# STM32_MCU.net
KiCad netlist of a schematic drawn in Altium Designer
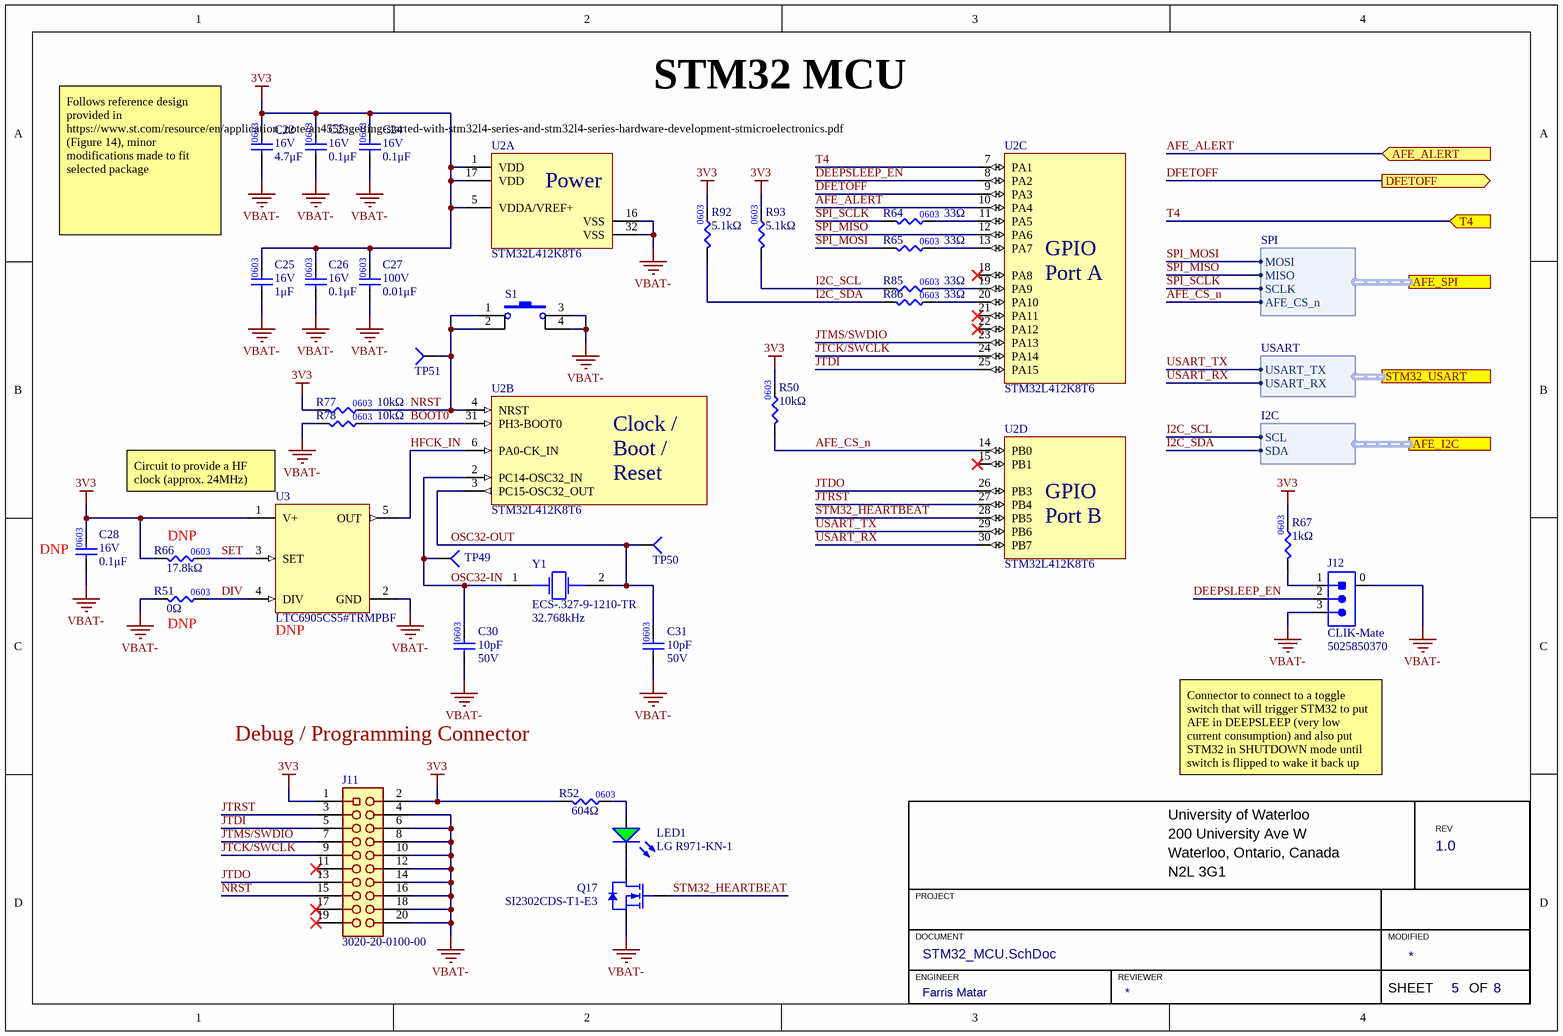
[diagram p0: STM32_MCU.SchDoc]

(export (version "E")
  (design (tool "Eeschema 10.0.6"))
  (components
    (comp (ref "C22")
      (value "4.7μF")
      (footprint "CAP0603")
      (description "CAP CER 4.7UF 16V X6S 0603")
      (fields (field (name "VOLTAGE RATING") "16V") (field (name "Comment") "CAP_4.7uF_16V_0603"))
      (libsource (lib "Personal_Schematic_Library_2022") (part "CAP_4.7uF_16V_0603"))
    )
    (comp (ref "C23")
      (value "0.1μF")
      (footprint "CAP0603")
      (description "CAP CER 0.1UF 16V X7R 0603")
      (fields (field (name "VOLTAGE RATING") "16V") (field (name "Comment") "CAP_0.1uF_16V_0603"))
      (libsource (lib "Personal_Schematic_Library_2022") (part "CAP_0.1uF_16V_0603"))
    )
    (comp (ref "C24")
      (value "0.1μF")
      (footprint "CAP0603")
      (description "CAP CER 0.1UF 16V X7R 0603")
      (fields (field (name "VOLTAGE RATING") "16V") (field (name "Comment") "CAP_0.1uF_16V_0603"))
      (libsource (lib "Personal_Schematic_Library_2022") (part "CAP_0.1uF_16V_0603"))
    )
    (comp (ref "C25")
      (value "1μF")
      (footprint "CAP0603")
      (description "CAP CER 1UF 16V X7R 0603")
      (fields (field (name "VOLTAGE RATING") "16V") (field (name "Comment") "CAP_1uF_16V_0603"))
      (libsource (lib "Personal_Schematic_Library_2022") (part "CAP_1uF_16V_0603"))
    )
    (comp (ref "C26")
      (value "0.1μF")
      (footprint "CAP0603")
      (description "CAP CER 0.1UF 16V X7R 0603")
      (fields (field (name "VOLTAGE RATING") "16V") (field (name "Comment") "CAP_0.1uF_16V_0603"))
      (libsource (lib "Personal_Schematic_Library_2022") (part "CAP_0.1uF_16V_0603"))
    )
    (comp (ref "C27")
      (value "0.01μF")
      (footprint "CAP0603")
      (description "CAP CER 0.01uF 100V X7R 0603")
      (fields (field (name "VOLTAGE RATING") "100V") (field (name "Comment") "CAP_0.01uF_100V_0603"))
      (libsource (lib "Personal_Schematic_Library_2022") (part "CAP_0.01uF_100V_0603"))
    )
    (comp (ref "C28")
      (value "0.1μF")
      (footprint "CAP0603")
      (description "CAP CER 0.1UF 16V X7R 0603")
      (fields (field (name "VOLTAGE RATING") "16V") (field (name "Comment") "CAP_0.1uF_16V_0603"))
      (libsource (lib "Personal_Schematic_Library_2022") (part "CAP_0.1uF_16V_0603"))
    )
    (comp (ref "C30")
      (value "10pF")
      (footprint "CAP0603")
      (description "CAP CER 10PF 50V X7R 0603")
      (fields (field (name "VOLTAGE RATING") "50V") (field (name "Comment") "CAP_10pF_50V_0603"))
      (libsource (lib "Personal_Schematic_Library_2022") (part "CAP_10pF_50V_0603"))
    )
    (comp (ref "C31")
      (value "10pF")
      (footprint "CAP0603")
      (description "CAP CER 10PF 50V X7R 0603")
      (fields (field (name "VOLTAGE RATING") "50V") (field (name "Comment") "CAP_10pF_50V_0603"))
      (libsource (lib "Personal_Schematic_Library_2022") (part "CAP_10pF_50V_0603"))
    )
    (comp (ref "J11")
      (value "3020-20-0100-00")
      (footprint "CNC_3020-20-0100-00")
      (description "CONN HEADER VERT 20POS 2.54MM")
      (libsource (lib "Personal_Schematic_Library_2022") (part "CON_10x2_HEADER"))
    )
    (comp (ref "J12")
      (value "CON_3M_SM_RA")
      (footprint "MOLEX-5025850370")
      (description "CONN RCPT 3POS 0.059 TIN SMD R/A")
      (fields (field (name "FAMILY") "CLIK-Mate") (field (name "MANUFACTURER PART NUMBER 1") "5025850370"))
      (libsource (lib "Personal_Schematic_Library_2022") (part "CON_3M_SM_RA"))
    )
    (comp (ref "LED1")
      (value "LED_GREEN")
      (footprint "LED_0805_GREEN")
      (description "LED GREEN DIFFUSED 0805 SMD")
      (fields (field (name "MANUFACTURER PART NUMBER 1") "LG R971-KN-1"))
      (libsource (lib "Personal_Schematic_Library_2022") (part "LED_GREEN"))
    )
    (comp (ref "Q17")
      (value "NMOS_20V_6A")
      (footprint "SOT23-3")
      (description "MOSFET N-CH 20V 2.6A SOT23-3")
      (fields (field (name "MANUFACTURER PART NUMBER 1") "SI2302CDS-T1-E3"))
      (libsource (lib "Personal_Schematic_Library_2022") (part "NMOS_20V_2.6A"))
    )
    (comp (ref "R50")
      (value "10kΩ")
      (footprint "RES0603")
      (description "RES 10K OHM 1% 1/8W 0603")
      (fields (field (name "Comment") "RES_10kΩ_0603_1%"))
      (libsource (lib "Personal_Schematic_Library_2022") (part "RES_10kΩ_0603_1%"))
    )
    (comp (ref "R51")
      (value "0Ω")
      (footprint "RES0603")
      (description "RES 0 OHM JUMPER 1/10W 0603")
      (fields (field (name "Comment") "RES_0Ω_0603"))
      (libsource (lib "Personal_Schematic_Library_2022") (part "RES_0Ω_0603"))
    )
    (comp (ref "R52")
      (value "604Ω")
      (footprint "RES0603")
      (description "RES 604 OHM 1% 1/10W 0603")
      (fields (field (name "Comment") "RES_604Ω_0603_1%"))
      (libsource (lib "Personal_Schematic_Library_2022") (part "RES_604Ω_0603_1%"))
    )
    (comp (ref "R64")
      (value "33Ω")
      (footprint "RES0603")
      (description "RES 33 OHM 1% 1/10W 0603")
      (fields (field (name "Comment") "RES_33Ω_0603_1%"))
      (libsource (lib "Personal_Schematic_Library_2022") (part "RES_33Ω_0603_1%"))
    )
    (comp (ref "R65")
      (value "33Ω")
      (footprint "RES0603")
      (description "RES 33 OHM 1% 1/10W 0603")
      (fields (field (name "Comment") "RES_33Ω_0603_1%"))
      (libsource (lib "Personal_Schematic_Library_2022") (part "RES_33Ω_0603_1%"))
    )
    (comp (ref "R66")
      (value "17.8kΩ")
      (footprint "RES0603")
      (description "RES 17.8K OHM 1% 1/10W 0603")
      (fields (field (name "Comment") "RES_17.8kΩ_0603_1%"))
      (libsource (lib "Personal_Schematic_Library_2022") (part "RES_17.8kΩ_0603_1%"))
    )
    (comp (ref "R67")
      (value "1kΩ")
      (footprint "RES0603")
      (description "RES 1K OHM 1% 1/8W 0603")
      (fields (field (name "Comment") "RES_1kΩ_0603_1%"))
      (libsource (lib "Personal_Schematic_Library_2022") (part "RES_1kΩ_0603_1%"))
    )
    (comp (ref "R77")
      (value "10kΩ")
      (footprint "RES0603")
      (description "RES 10K OHM 1% 1/8W 0603")
      (fields (field (name "Comment") "RES_10kΩ_0603_1%"))
      (libsource (lib "Personal_Schematic_Library_2022") (part "RES_10kΩ_0603_1%"))
    )
    (comp (ref "R78")
      (value "10kΩ")
      (footprint "RES0603")
      (description "RES 10K OHM 1% 1/8W 0603")
      (fields (field (name "Comment") "RES_10kΩ_0603_1%"))
      (libsource (lib "Personal_Schematic_Library_2022") (part "RES_10kΩ_0603_1%"))
    )
    (comp (ref "R85")
      (value "33Ω")
      (footprint "RES0603")
      (description "RES 33 OHM 1% 1/10W 0603")
      (fields (field (name "Comment") "RES_33Ω_0603_1%"))
      (libsource (lib "Personal_Schematic_Library_2022") (part "RES_33Ω_0603_1%"))
    )
    (comp (ref "R86")
      (value "33Ω")
      (footprint "RES0603")
      (description "RES 33 OHM 1% 1/10W 0603")
      (fields (field (name "Comment") "RES_33Ω_0603_1%"))
      (libsource (lib "Personal_Schematic_Library_2022") (part "RES_33Ω_0603_1%"))
    )
    (comp (ref "R92")
      (value "5.1kΩ")
      (footprint "RES0603")
      (description "RES 5.1K OHM 1% 1/10W 0603")
      (fields (field (name "Comment") "RES_5.1kΩ_0603_1%"))
      (libsource (lib "Personal_Schematic_Library_2022") (part "RES_5.1kΩ_0603_1%"))
    )
    (comp (ref "R93")
      (value "5.1kΩ")
      (footprint "RES0603")
      (description "RES 5.1K OHM 1% 1/10W 0603")
      (fields (field (name "Comment") "RES_5.1kΩ_0603_1%"))
      (libsource (lib "Personal_Schematic_Library_2022") (part "RES_5.1kΩ_0603_1%"))
    )
    (comp (ref "S1")
      (value "SW_SPST_NO_4.5x4.5")
      (footprint "SPST_PUSHBUTTON_TL3305AF260QG")
      (description "SWITCH TACTILE SPST-NO 50MA 12V")
      (libsource (lib "Personal_Schematic_Library_2022") (part "SW_SPST_NO_4.5x4.5"))
    )
    (comp (ref "TP49")
      (value "TESTPOINT_1MM_CIRCLE")
      (footprint "TESTPOINT_CIRCLE_1MM")
      (description "TESTPOINT 1MM CIRCLE")
      (libsource (lib "Personal_Schematic_Library_2022") (part "TESTPOINT_1MM_CIRCLE"))
    )
    (comp (ref "TP50")
      (value "TESTPOINT_1MM_CIRCLE")
      (footprint "TESTPOINT_CIRCLE_1MM")
      (description "TESTPOINT 1MM CIRCLE")
      (libsource (lib "Personal_Schematic_Library_2022") (part "TESTPOINT_1MM_CIRCLE"))
    )
    (comp (ref "TP51")
      (value "TESTPOINT_1MM_CIRCLE")
      (footprint "TESTPOINT_CIRCLE_1MM")
      (description "TESTPOINT 1MM CIRCLE")
      (libsource (lib "Personal_Schematic_Library_2022") (part "TESTPOINT_1MM_CIRCLE"))
    )
    (comp (ref "U2")
      (value "STM32L412K8T6")
      (footprint "STM-LQFP32")
      (description "IC MCU 32BIT 64KB FLASH 32LQFP")
      (libsource (lib "Personal_Schematic_Library_2022") (part "STM32L412K8T6"))
    )
    (comp (ref "U3")
      (value "LTC6905CS5#TRMPBF")
      (footprint "SOT23-5")
      (description "IC OSC SILICON PROG TSOT23-5")
      (libsource (lib "Personal_Schematic_Library_2022") (part "IC_OSC_LTC6905"))
    )
    (comp (ref "Y1")
      (value "CRYSTAL_32.768KHZ")
      (footprint "OSC_ECS-327TR-2")
      (description "CRYSTAL 32.7680KHZ 9PF SMD")
      (fields
        (field (name "FREQUENCY") "32.768kHz")
        (field (name "MANUFACTURER PART NUMBER 1") "ECS-.327-9-1210-TR")
      )
      (libsource (lib "Personal_Schematic_Library_2022") (part "CRYSTAL_32.768KHZ"))
    )
  )
  (nets
    (net (code "4") (name "/AFE_ALERT") (class "Default")
      (node (ref "U2") (pin "10") (pinfunction "PA4_10") (pintype "bidirectional"))
    )
    (net (code "5") (name "/AFE_CS_n") (class "Default")
      (node (ref "R50") (pin "1") (pinfunction "1_1") (pintype "passive"))
      (node (ref "U2") (pin "14") (pinfunction "PB0_14") (pintype "bidirectional"))
    )
    (net (code "6") (name "/BOOT0") (class "Default")
      (node (ref "R78") (pin "2") (pinfunction "2_2") (pintype "passive"))
      (node (ref "U2") (pin "31") (pinfunction "PH3-BOOT0_31") (pintype "input"))
    )
    (net (code "7") (name "/DEEPSLEEP_EN") (class "Default")
      (node (ref "J12") (pin "2") (pinfunction "2_2") (pintype "passive"))
      (node (ref "U2") (pin "8") (pinfunction "PA2_8") (pintype "bidirectional"))
    )
    (net (code "8") (name "/DFETOFF") (class "Default")
      (node (ref "U2") (pin "9") (pinfunction "PA3_9") (pintype "bidirectional"))
    )
    (net (code "9") (name "/DIV") (class "Default")
      (node (ref "R51") (pin "2") (pinfunction "2_2") (pintype "passive"))
      (node (ref "U3") (pin "4") (pinfunction "DIV_4") (pintype "input"))
    )
    (net (code "10") (name "/HFCK_IN") (class "Default")
      (node (ref "U2") (pin "6") (pinfunction "PA0-CK_IN_6") (pintype "input"))
      (node (ref "U3") (pin "5") (pinfunction "OUT_5") (pintype "output"))
    )
    (net (code "11") (name "/I2C_SCL") (class "Default")
      (node (ref "R85") (pin "1") (pinfunction "1_1") (pintype "passive"))
      (node (ref "R93") (pin "1") (pinfunction "1_1") (pintype "passive"))
    )
    (net (code "12") (name "/I2C_SDA") (class "Default")
      (node (ref "R86") (pin "1") (pinfunction "1_1") (pintype "passive"))
      (node (ref "R92") (pin "1") (pinfunction "1_1") (pintype "passive"))
    )
    (net (code "13") (name "/JTCK{slash}SWCLK") (class "Default")
      (node (ref "J11") (pin "9") (pinfunction "9_9") (pintype "passive"))
      (node (ref "U2") (pin "24") (pinfunction "PA14_24") (pintype "bidirectional"))
    )
    (net (code "14") (name "/JTDI") (class "Default")
      (node (ref "J11") (pin "5") (pinfunction "5_5") (pintype "passive"))
      (node (ref "U2") (pin "25") (pinfunction "PA15_25") (pintype "bidirectional"))
    )
    (net (code "15") (name "/JTDO") (class "Default")
      (node (ref "J11") (pin "13") (pinfunction "13_13") (pintype "passive"))
      (node (ref "U2") (pin "26") (pinfunction "PB3_26") (pintype "bidirectional"))
    )
    (net (code "16") (name "/JTMS{slash}SWDIO") (class "Default")
      (node (ref "J11") (pin "7") (pinfunction "7_7") (pintype "passive"))
      (node (ref "U2") (pin "23") (pinfunction "PA13_23") (pintype "bidirectional"))
    )
    (net (code "17") (name "/JTRST") (class "Default")
      (node (ref "J11") (pin "3") (pinfunction "3_3") (pintype "passive"))
      (node (ref "U2") (pin "27") (pinfunction "PB4_27") (pintype "bidirectional"))
    )
    (net (code "18") (name "/NRST") (class "Default")
      (node (ref "J11") (pin "15") (pinfunction "15_15") (pintype "passive"))
      (node (ref "R77") (pin "2") (pinfunction "2_2") (pintype "passive"))
      (node (ref "S1") (pin "1") (pinfunction "1_1") (pintype "passive"))
      (node (ref "S1") (pin "2") (pinfunction "2_2") (pintype "passive"))
      (node (ref "TP51") (pin "1") (pinfunction "=value_1") (pintype "passive"))
      (node (ref "U2") (pin "4") (pinfunction "NRST_4") (pintype "input"))
    )
    (net (code "19") (name "/OSC32-IN") (class "Default")
      (node (ref "C30") (pin "2") (pinfunction "2_2") (pintype "passive"))
      (node (ref "TP49") (pin "1") (pinfunction "=value_1") (pintype "passive"))
      (node (ref "U2") (pin "2") (pinfunction "PC14-OSC32_IN_2") (pintype "input"))
      (node (ref "Y1") (pin "1") (pinfunction "1_1") (pintype "passive"))
    )
    (net (code "20") (name "/OSC32-OUT") (class "Default")
      (node (ref "C31") (pin "2") (pinfunction "2_2") (pintype "passive"))
      (node (ref "TP50") (pin "1") (pinfunction "=value_1") (pintype "passive"))
      (node (ref "U2") (pin "3") (pinfunction "PC15-OSC32_OUT_3") (pintype "output"))
      (node (ref "Y1") (pin "2") (pinfunction "2_2") (pintype "passive"))
    )
    (net (code "21") (name "/SET") (class "Default")
      (node (ref "R66") (pin "2") (pinfunction "2_2") (pintype "passive"))
      (node (ref "U3") (pin "3") (pinfunction "SET_3") (pintype "input"))
    )
    (net (code "22") (name "/SPI_MISO") (class "Default")
      (node (ref "U2") (pin "12") (pinfunction "PA6_12") (pintype "bidirectional"))
    )
    (net (code "23") (name "/SPI_MOSI") (class "Default")
      (node (ref "R65") (pin "1") (pinfunction "1_1") (pintype "passive"))
    )
    (net (code "24") (name "/SPI_SCLK") (class "Default")
      (node (ref "R64") (pin "1") (pinfunction "1_1") (pintype "passive"))
    )
    (net (code "25") (name "/STM32_HEARTBEAT") (class "Default")
      (node (ref "Q17") (pin "1") (pinfunction "GATE_1") (pintype "passive"))
      (node (ref "U2") (pin "28") (pinfunction "PB5_28") (pintype "bidirectional"))
    )
    (net (code "26") (name "/T4") (class "Default")
      (node (ref "U2") (pin "7") (pinfunction "PA1_7") (pintype "bidirectional"))
    )
    (net (code "27") (name "/USART_RX") (class "Default")
      (node (ref "U2") (pin "30") (pinfunction "PB7_30") (pintype "bidirectional"))
    )
    (net (code "28") (name "/USART_TX") (class "Default")
      (node (ref "U2") (pin "29") (pinfunction "PB6_29") (pintype "bidirectional"))
    )
    (net (code "32") (name "3V3") (class "Default")
      (node (ref "C22") (pin "2") (pinfunction "2_2") (pintype "passive"))
      (node (ref "C23") (pin "2") (pinfunction "2_2") (pintype "passive"))
      (node (ref "C24") (pin "2") (pinfunction "2_2") (pintype "passive"))
      (node (ref "C25") (pin "2") (pinfunction "2_2") (pintype "passive"))
      (node (ref "C26") (pin "2") (pinfunction "2_2") (pintype "passive"))
      (node (ref "C27") (pin "2") (pinfunction "2_2") (pintype "passive"))
      (node (ref "C28") (pin "2") (pinfunction "2_2") (pintype "passive"))
      (node (ref "J11") (pin "1") (pinfunction "1_1") (pintype "passive"))
      (node (ref "J11") (pin "2") (pinfunction "2_2") (pintype "passive"))
      (node (ref "R50") (pin "2") (pinfunction "2_2") (pintype "passive"))
      (node (ref "R52") (pin "1") (pinfunction "1_1") (pintype "passive"))
      (node (ref "R66") (pin "1") (pinfunction "1_1") (pintype "passive"))
      (node (ref "R67") (pin "2") (pinfunction "2_2") (pintype "passive"))
      (node (ref "R77") (pin "1") (pinfunction "1_1") (pintype "passive"))
      (node (ref "R92") (pin "2") (pinfunction "2_2") (pintype "passive"))
      (node (ref "R93") (pin "2") (pinfunction "2_2") (pintype "passive"))
      (node (ref "U2") (pin "1") (pinfunction "VDD_1") (pintype "power_in"))
      (node (ref "U2") (pin "17") (pinfunction "VDD_17") (pintype "power_in"))
      (node (ref "U2") (pin "5") (pinfunction "VDDA/VREF+_5") (pintype "power_in"))
      (node (ref "U3") (pin "1") (pinfunction "V+_1") (pintype "power_in"))
    )
    (net (code "33") (name "Net-(J12-Pad1)") (class "Default")
      (node (ref "J12") (pin "1") (pinfunction "1_1") (pintype "passive"))
      (node (ref "R67") (pin "1") (pinfunction "1_1") (pintype "passive"))
    )
    (net (code "34") (name "Net-(LED1-A)") (class "Default")
      (node (ref "LED1") (pin "1") (pinfunction "A_1") (pintype "passive"))
      (node (ref "R52") (pin "2") (pinfunction "2_2") (pintype "passive"))
    )
    (net (code "35") (name "Net-(LED1-K)") (class "Default")
      (node (ref "LED1") (pin "2") (pinfunction "K_2") (pintype "passive"))
      (node (ref "Q17") (pin "3") (pinfunction "DRAIN_3") (pintype "passive"))
    )
    (net (code "36") (name "Net-(U2C-PA5)") (class "Default")
      (node (ref "R64") (pin "2") (pinfunction "2_2") (pintype "passive"))
      (node (ref "U2") (pin "11") (pinfunction "PA5_11") (pintype "bidirectional"))
    )
    (net (code "37") (name "Net-(U2C-PA7)") (class "Default")
      (node (ref "R65") (pin "2") (pinfunction "2_2") (pintype "passive"))
      (node (ref "U2") (pin "13") (pinfunction "PA7_13") (pintype "bidirectional"))
    )
    (net (code "38") (name "Net-(U2C-PA9)") (class "Default")
      (node (ref "R85") (pin "2") (pinfunction "2_2") (pintype "passive"))
      (node (ref "U2") (pin "19") (pinfunction "PA9_19") (pintype "bidirectional"))
    )
    (net (code "39") (name "Net-(U2C-PA10)") (class "Default")
      (node (ref "R86") (pin "2") (pinfunction "2_2") (pintype "passive"))
      (node (ref "U2") (pin "20") (pinfunction "PA10_20") (pintype "bidirectional"))
    )
    (net (code "40") (name "VBAT-") (class "Default")
      (node (ref "C22") (pin "1") (pinfunction "1_1") (pintype "passive"))
      (node (ref "C23") (pin "1") (pinfunction "1_1") (pintype "passive"))
      (node (ref "C24") (pin "1") (pinfunction "1_1") (pintype "passive"))
      (node (ref "C25") (pin "1") (pinfunction "1_1") (pintype "passive"))
      (node (ref "C26") (pin "1") (pinfunction "1_1") (pintype "passive"))
      (node (ref "C27") (pin "1") (pinfunction "1_1") (pintype "passive"))
      (node (ref "C28") (pin "1") (pinfunction "1_1") (pintype "passive"))
      (node (ref "C30") (pin "1") (pinfunction "1_1") (pintype "passive"))
      (node (ref "C31") (pin "1") (pinfunction "1_1") (pintype "passive"))
      (node (ref "J11") (pin "10") (pinfunction "10_10") (pintype "passive"))
      (node (ref "J11") (pin "12") (pinfunction "12_12") (pintype "passive"))
      (node (ref "J11") (pin "14") (pinfunction "14_14") (pintype "passive"))
      (node (ref "J11") (pin "16") (pinfunction "16_16") (pintype "passive"))
      (node (ref "J11") (pin "18") (pinfunction "18_18") (pintype "passive"))
      (node (ref "J11") (pin "20") (pinfunction "20_20") (pintype "passive"))
      (node (ref "J11") (pin "4") (pinfunction "4_4") (pintype "passive"))
      (node (ref "J11") (pin "6") (pinfunction "6_6") (pintype "passive"))
      (node (ref "J11") (pin "8") (pinfunction "8_8") (pintype "passive"))
      (node (ref "J12") (pin "0") (pinfunction "0_0") (pintype "passive"))
      (node (ref "J12") (pin "3") (pinfunction "3_3") (pintype "passive"))
      (node (ref "Q17") (pin "2") (pinfunction "SOURCE_2") (pintype "passive"))
      (node (ref "R51") (pin "1") (pinfunction "1_1") (pintype "passive"))
      (node (ref "R78") (pin "1") (pinfunction "1_1") (pintype "passive"))
      (node (ref "S1") (pin "3") (pinfunction "3_3") (pintype "passive"))
      (node (ref "S1") (pin "4") (pinfunction "4_4") (pintype "passive"))
      (node (ref "U2") (pin "16") (pinfunction "VSS_16") (pintype "power_in"))
      (node (ref "U2") (pin "32") (pinfunction "VSS_32") (pintype "power_in"))
      (node (ref "U3") (pin "2") (pinfunction "GND_2") (pintype "power_in"))
    )
    (net (code "41") (name "unconnected-(J11-Pad11)") (class "Default")
      (node (ref "J11") (pin "11") (pinfunction "11_11") (pintype "passive+no_connect"))
    )
    (net (code "42") (name "unconnected-(J11-Pad17)") (class "Default")
      (node (ref "J11") (pin "17") (pinfunction "17_17") (pintype "passive+no_connect"))
    )
    (net (code "43") (name "unconnected-(J11-Pad19)") (class "Default")
      (node (ref "J11") (pin "19") (pinfunction "19_19") (pintype "passive+no_connect"))
    )
    (net (code "44") (name "unconnected-(U2C-PA8-Pad18)") (class "Default")
      (node (ref "U2") (pin "18") (pinfunction "PA8_18") (pintype "bidirectional+no_connect"))
    )
    (net (code "45") (name "unconnected-(U2C-PA11-Pad21)") (class "Default")
      (node (ref "U2") (pin "21") (pinfunction "PA11_21") (pintype "bidirectional+no_connect"))
    )
    (net (code "46") (name "unconnected-(U2C-PA12-Pad22)") (class "Default")
      (node (ref "U2") (pin "22") (pinfunction "PA12_22") (pintype "bidirectional+no_connect"))
    )
    (net (code "47") (name "unconnected-(U2D-PB1-Pad15)") (class "Default")
      (node (ref "U2") (pin "15") (pinfunction "PB1_15") (pintype "bidirectional+no_connect"))
    )
  )
)
